# LCD_board.net
KiCad netlist of a schematic drawn in EAGLE
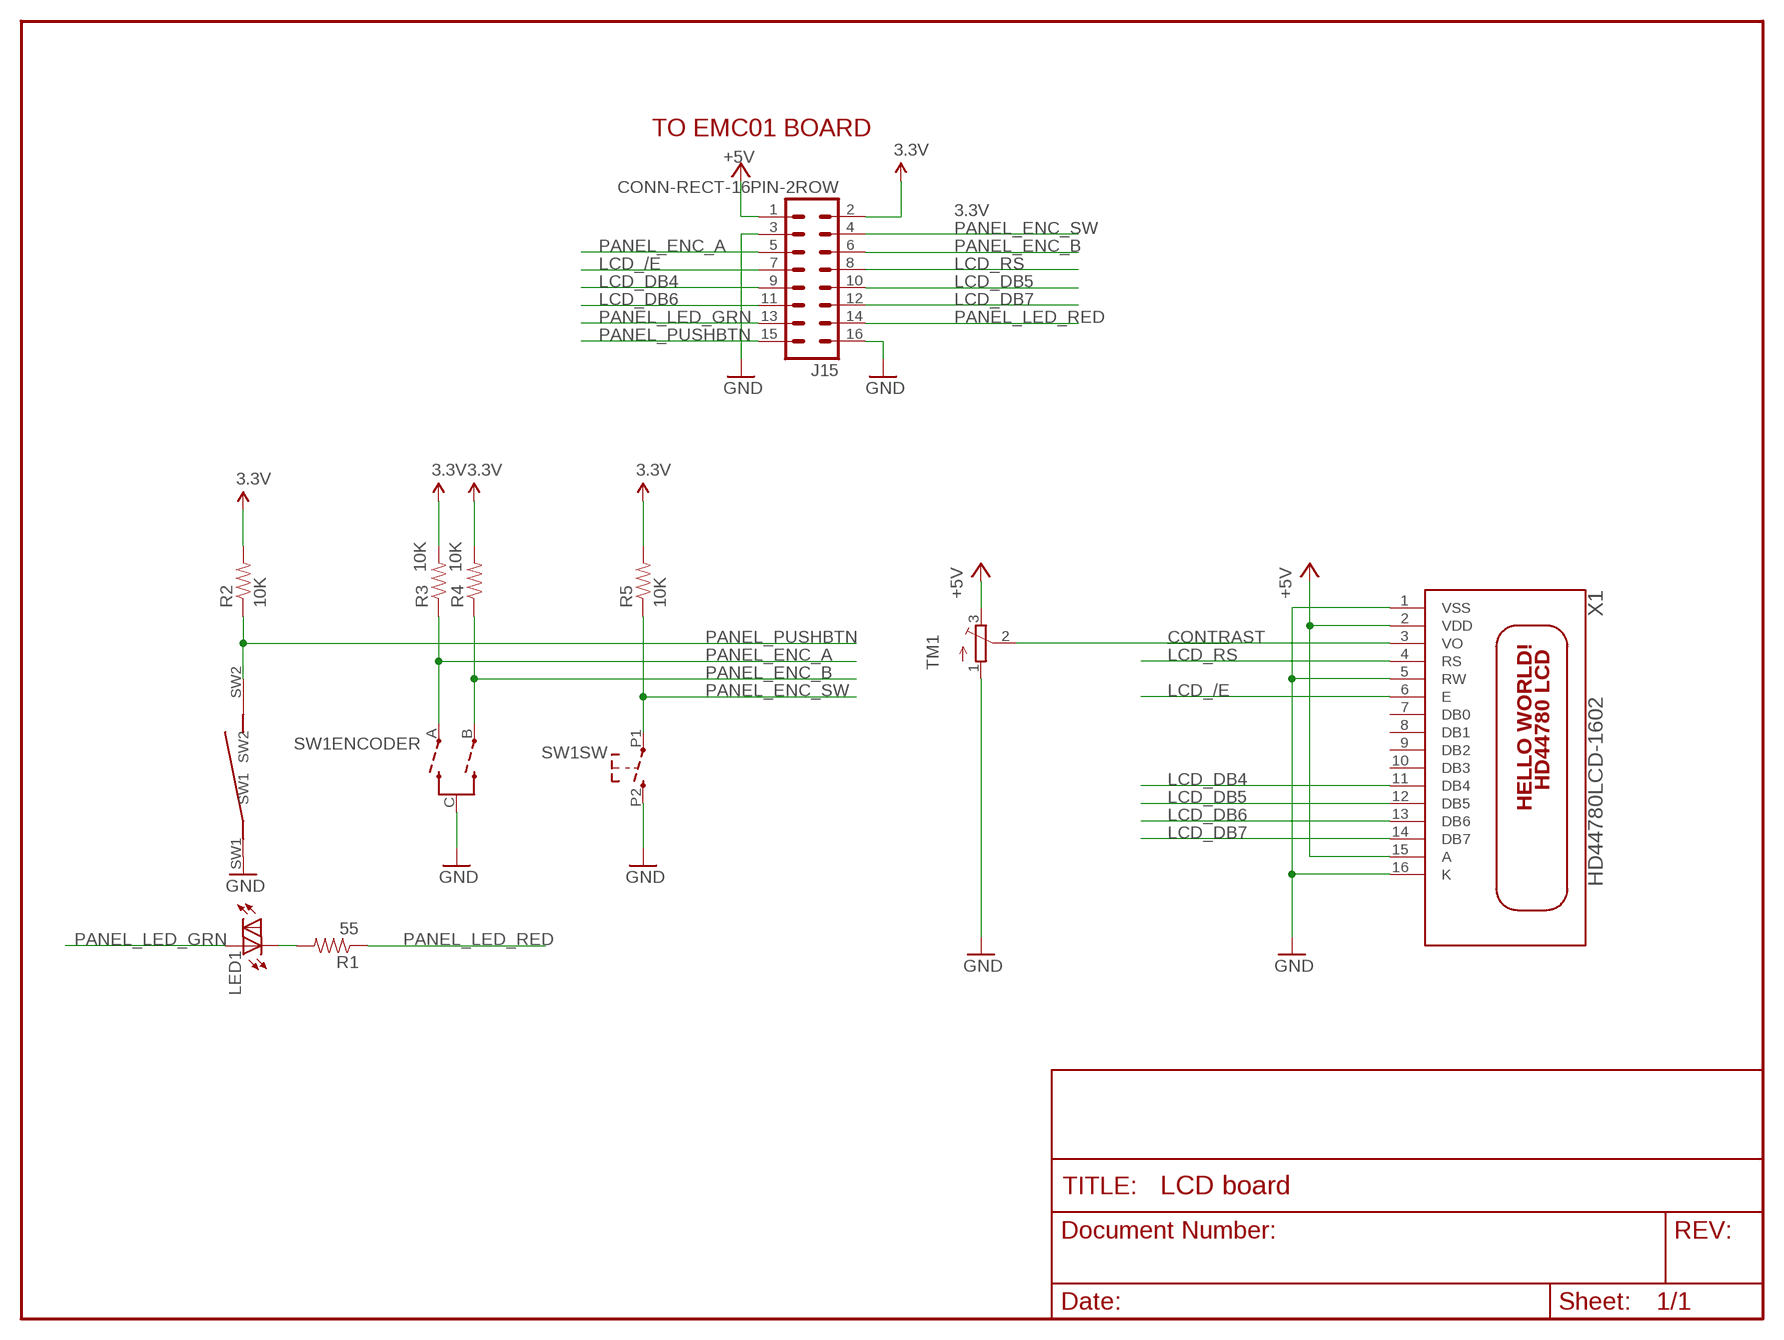
[diagram p0: schematic, sheet 1]

(export (version "E")
  (design (tool "Eeschema 10.0.6"))
  (components
    (comp (ref "J15")
      (value "CONN-RECT-16PIN-2ROW")
      (footprint "eagle-import:CONN-RECT-2.54MM-16PIN-2ROW-SMTH")
      (libsource (lib "eagle-import") (part "CONN-RECT-16PIN-2ROW"))
    )
    (comp (ref "LED1")
      (value "LED-BUTTON")
      (footprint "eagle-import:ELAST_PAD_SQUARE_10MM_5.4MM_4X4GRID")
      (libsource (lib "eagle-import") (part "LED-BUTTON"))
    )
    (comp (ref "R1")
      (value "55")
      (footprint "eagle-import:0805")
      (libsource (lib "eagle-import") (part "RESISTOR0805-RES"))
    )
    (comp (ref "R2")
      (value "10K")
      (footprint "eagle-import:0805")
      (libsource (lib "eagle-import") (part "RESISTOR0805-RES"))
    )
    (comp (ref "R3")
      (value "10K")
      (footprint "eagle-import:0805")
      (libsource (lib "eagle-import") (part "RESISTOR0805-RES"))
    )
    (comp (ref "R4")
      (value "10K")
      (footprint "eagle-import:0805")
      (libsource (lib "eagle-import") (part "RESISTOR0805-RES"))
    )
    (comp (ref "R5")
      (value "10K")
      (footprint "eagle-import:0805")
      (libsource (lib "eagle-import") (part "RESISTOR0805-RES"))
    )
    (comp (ref "SW1")
      (value "ENCODER_SW1-PEC12")
      (footprint "eagle-import:PEC12_INCREMENTAL_ENCODER")
      (libsource (lib "eagle-import") (part "ENCODER_SW1-PEC12"))
    )
    (comp (ref "TM1")
      (value "TRIMPOTTC33X")
      (footprint "eagle-import:TC33X")
      (libsource (lib "eagle-import") (part "TRIMPOTTC33X"))
    )
    (comp (ref "X1")
      (value "HD44780LCD-1602")
      (footprint "eagle-import:LCD1602")
      (libsource (lib "eagle-import") (part "HD44780LCD-1602"))
    )
  )
  (nets
    (net (code "1") (name "+5V") (class "Default")
      (node (ref "J15") (pin "1") (pinfunction "1_1") (pintype "passive"))
      (node (ref "TM1") (pin "3") (pinfunction "E_3") (pintype "passive"))
      (node (ref "X1") (pin "15") (pinfunction "A_15") (pintype "input"))
      (node (ref "X1") (pin "2") (pinfunction "VDD_2") (pintype "power_in"))
    )
    (net (code "2") (name "/CONTRAST") (class "Default")
      (node (ref "TM1") (pin "2") (pinfunction "S_2") (pintype "passive"))
      (node (ref "X1") (pin "3") (pinfunction "VO_3") (pintype "input"))
    )
    (net (code "3") (name "/LCD_DB4") (class "Default")
      (node (ref "J15") (pin "9") (pinfunction "9_9") (pintype "passive"))
      (node (ref "X1") (pin "11") (pinfunction "DB4_11") (pintype "bidirectional"))
    )
    (net (code "4") (name "/LCD_DB5") (class "Default")
      (node (ref "J15") (pin "10") (pinfunction "10_10") (pintype "passive"))
      (node (ref "X1") (pin "12") (pinfunction "DB5_12") (pintype "bidirectional"))
    )
    (net (code "5") (name "/LCD_DB6") (class "Default")
      (node (ref "J15") (pin "11") (pinfunction "11_11") (pintype "passive"))
      (node (ref "X1") (pin "13") (pinfunction "DB6_13") (pintype "bidirectional"))
    )
    (net (code "6") (name "/LCD_DB7") (class "Default")
      (node (ref "J15") (pin "12") (pinfunction "12_12") (pintype "passive"))
      (node (ref "X1") (pin "14") (pinfunction "DB7_14") (pintype "bidirectional"))
    )
    (net (code "7") (name "/LCD_RS") (class "Default")
      (node (ref "J15") (pin "8") (pinfunction "8_8") (pintype "passive"))
      (node (ref "X1") (pin "4") (pinfunction "RS_4") (pintype "input"))
    )
    (net (code "8") (name "/LCD_{slash}E") (class "Default")
      (node (ref "J15") (pin "7") (pinfunction "7_7") (pintype "passive"))
      (node (ref "X1") (pin "6") (pinfunction "E_6") (pintype "input"))
    )
    (net (code "9") (name "/PANEL_ENC_A") (class "Default")
      (node (ref "J15") (pin "5") (pinfunction "5_5") (pintype "passive"))
      (node (ref "R3") (pin "1") (pinfunction "1_1") (pintype "passive"))
      (node (ref "SW1") (pin "A") (pinfunction "A_A") (pintype "passive"))
    )
    (net (code "10") (name "/PANEL_ENC_B") (class "Default")
      (node (ref "J15") (pin "6") (pinfunction "6_6") (pintype "passive"))
      (node (ref "R4") (pin "1") (pinfunction "1_1") (pintype "passive"))
      (node (ref "SW1") (pin "B") (pinfunction "B_B") (pintype "passive"))
    )
    (net (code "11") (name "/PANEL_ENC_SW") (class "Default")
      (node (ref "J15") (pin "4") (pinfunction "4_4") (pintype "passive"))
      (node (ref "R5") (pin "1") (pinfunction "1_1") (pintype "passive"))
      (node (ref "SW1") (pin "P1") (pinfunction "1_P1") (pintype "passive"))
    )
    (net (code "12") (name "/PANEL_LED_GRN") (class "Default")
      (node (ref "J15") (pin "13") (pinfunction "13_13") (pintype "passive"))
      (node (ref "LED1") (pin "A1") (pinfunction "A_A1") (pintype "bidirectional"))
    )
    (net (code "13") (name "/PANEL_LED_RED") (class "Default")
      (node (ref "J15") (pin "14") (pinfunction "14_14") (pintype "passive"))
      (node (ref "R1") (pin "1") (pinfunction "1_1") (pintype "passive"))
    )
    (net (code "14") (name "/PANEL_PUSHBTN") (class "Default")
      (node (ref "J15") (pin "15") (pinfunction "15_15") (pintype "passive"))
      (node (ref "LED1") (pin "SW2") (pinfunction "SW2_SW2") (pintype "bidirectional"))
      (node (ref "R2") (pin "1") (pinfunction "1_1") (pintype "passive"))
    )
    (net (code "15") (name "3.3V") (class "Default")
      (node (ref "J15") (pin "2") (pinfunction "2_2") (pintype "passive"))
      (node (ref "R2") (pin "2") (pinfunction "2_2") (pintype "passive"))
      (node (ref "R3") (pin "2") (pinfunction "2_2") (pintype "passive"))
      (node (ref "R4") (pin "2") (pinfunction "2_2") (pintype "passive"))
      (node (ref "R5") (pin "2") (pinfunction "2_2") (pintype "passive"))
    )
    (net (code "16") (name "GND") (class "Default")
      (node (ref "J15") (pin "16") (pinfunction "16_16") (pintype "passive"))
      (node (ref "J15") (pin "3") (pinfunction "3_3") (pintype "passive"))
      (node (ref "LED1") (pin "SW1") (pinfunction "SW1_SW1") (pintype "bidirectional"))
      (node (ref "SW1") (pin "C") (pinfunction "C_C") (pintype "passive"))
      (node (ref "SW1") (pin "P2") (pinfunction "2_P2") (pintype "passive"))
      (node (ref "TM1") (pin "1") (pinfunction "A_1") (pintype "passive"))
      (node (ref "X1") (pin "1") (pinfunction "VSS_1") (pintype "power_in"))
      (node (ref "X1") (pin "16") (pinfunction "K_16") (pintype "input"))
      (node (ref "X1") (pin "5") (pinfunction "RW_5") (pintype "input"))
    )
    (net (code "17") (name "Net-(LED1-C)") (class "Default")
      (node (ref "LED1") (pin "K") (pinfunction "C_K") (pintype "bidirectional"))
      (node (ref "R1") (pin "2") (pinfunction "2_2") (pintype "passive"))
    )
    (net (code "18") (name "unconnected-(X1-DB0-Pad7)") (class "Default")
      (node (ref "X1") (pin "7") (pinfunction "DB0_7") (pintype "bidirectional"))
    )
    (net (code "19") (name "unconnected-(X1-DB1-Pad8)") (class "Default")
      (node (ref "X1") (pin "8") (pinfunction "DB1_8") (pintype "bidirectional"))
    )
    (net (code "20") (name "unconnected-(X1-DB2-Pad9)") (class "Default")
      (node (ref "X1") (pin "9") (pinfunction "DB2_9") (pintype "bidirectional"))
    )
    (net (code "21") (name "unconnected-(X1-DB3-Pad10)") (class "Default")
      (node (ref "X1") (pin "10") (pinfunction "DB3_10") (pintype "bidirectional"))
    )
  )
)
